# 21_Peripherals.net
KiCad netlist of a schematic drawn in Altium Designer
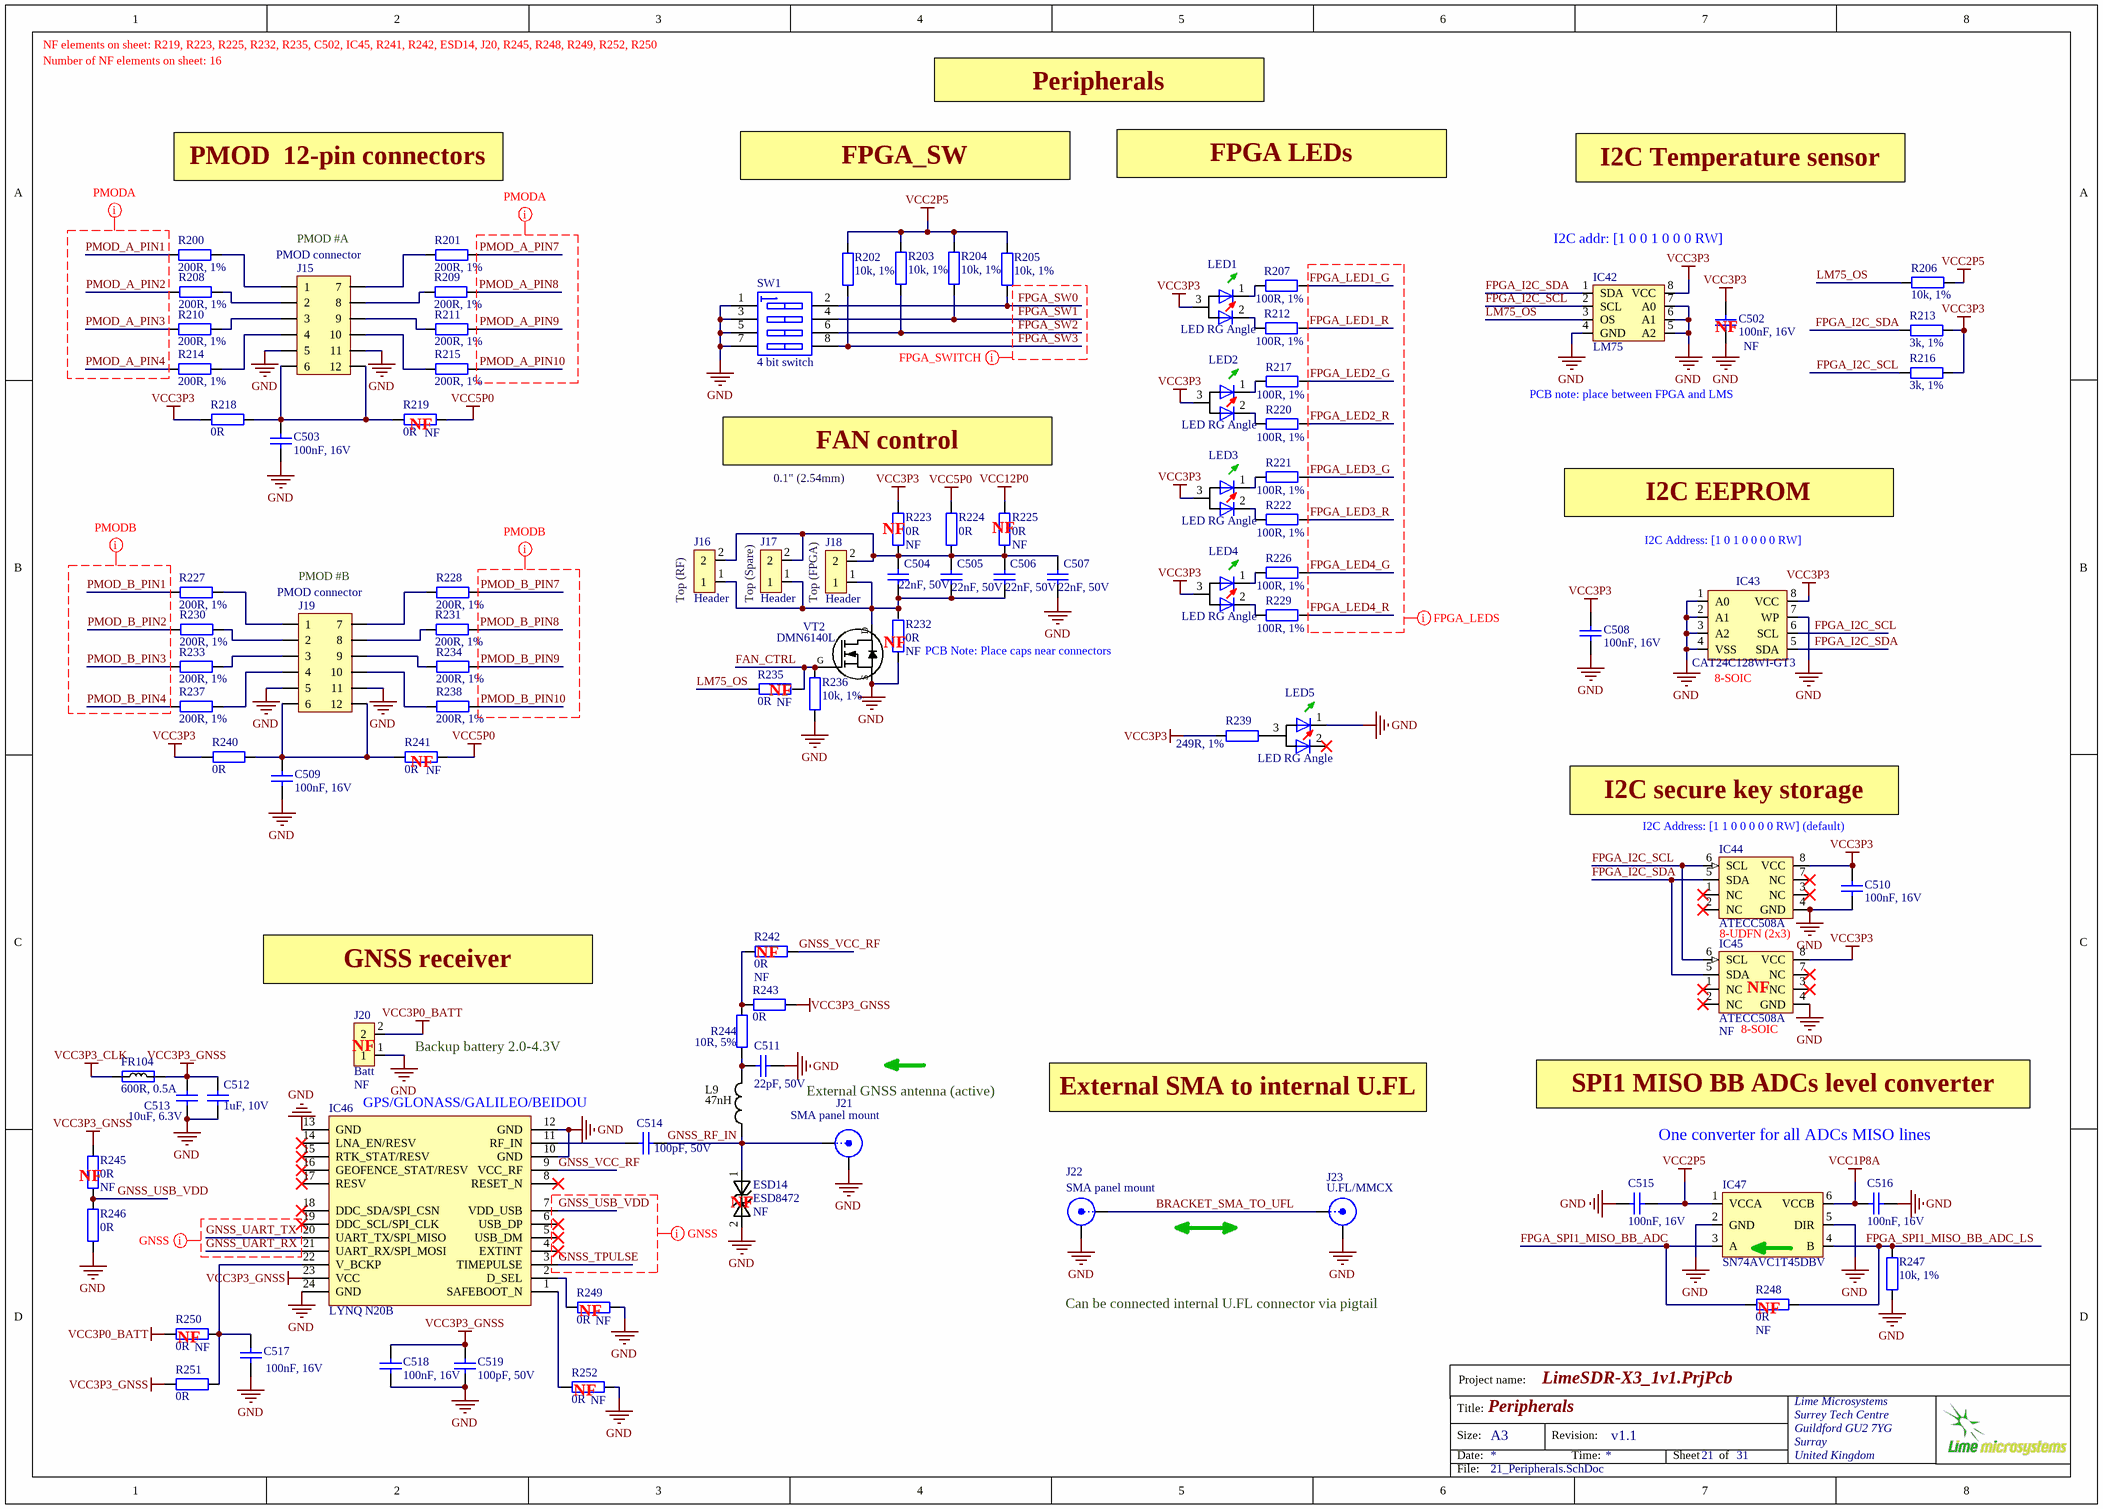
[diagram p0: 21_Peripherals.SchDoc]

(export (version "E")
  (design (tool "Eeschema 10.0.6"))
  (components
    (comp (ref "C502")
      (value "100nF, 16V")
      (footprint "CAP0402")
      (fields
        (field (name "TOLERANCE") "10 %")
        (field (name "MANUFACTURER") "Murata Electronics")
        (field (name "ASSEMBLY INFO") "NF")
      )
      (libsource (lib "") (part "Cap_0603_1"))
    )
    (comp (ref "C503")
      (value "100nF, 16V")
      (footprint "CAP0402")
      (fields
        (field (name "TOLERANCE") "10 %")
        (field (name "MANUFACTURER") "Murata Electronics")
        (field (name "MANUFACTURER PART NUMBER") "GRM155R71C104KA88D")
      )
      (libsource (lib "") (part "Cap_0603_3"))
    )
    (comp (ref "C504")
      (value "22nF, 50V")
      (footprint "CAP0402")
      (fields (field (name "TOLERANCE") "±10%") (field (name "MANUFACTURER") "Kemet"))
      (libsource (lib "") (part "Cap_0402_2"))
    )
    (comp (ref "C505")
      (value "22nF, 50V")
      (footprint "CAP0402")
      (fields (field (name "TOLERANCE") "±10%") (field (name "MANUFACTURER") "Kemet"))
      (libsource (lib "") (part "Cap_0402_1"))
    )
    (comp (ref "C506")
      (value "22nF, 50V")
      (footprint "CAP0402")
      (fields (field (name "TOLERANCE") "±10%") (field (name "MANUFACTURER") "Kemet"))
      (libsource (lib "") (part "Cap_0402_1"))
    )
    (comp (ref "C507")
      (value "22nF, 50V")
      (footprint "CAP0402")
      (fields (field (name "TOLERANCE") "±10%") (field (name "MANUFACTURER") "Kemet"))
      (libsource (lib "") (part "Cap_0402_1"))
    )
    (comp (ref "C508")
      (value "100nF, 16V")
      (footprint "CAP0402")
      (fields (field (name "TOLERANCE") "10 %") (field (name "MANUFACTURER") "Murata Electronics"))
      (libsource (lib "") (part "Cap_0603_2"))
    )
    (comp (ref "C509")
      (value "100nF, 16V")
      (footprint "CAP0402")
      (fields
        (field (name "TOLERANCE") "10 %")
        (field (name "MANUFACTURER") "Murata Electronics")
        (field (name "MANUFACTURER PART NUMBER") "GRM155R71C104KA88D")
      )
      (libsource (lib "") (part "Cap_0603_3"))
    )
    (comp (ref "C510")
      (value "100nF, 16V")
      (footprint "CAP0402")
      (fields (field (name "TOLERANCE") "10 %") (field (name "MANUFACTURER") "Murata Electronics"))
      (libsource (lib "") (part "Cap_0603_2"))
    )
    (comp (ref "C511")
      (value "22pF, 50V")
      (footprint "CAP0402")
      (fields (field (name "TOLERANCE") "±5%") (field (name "MANUFACTURER") "Yageo"))
      (libsource (lib "LimeMicroAltiumLib_schLib") (part "Cap_0402"))
    )
    (comp (ref "C512")
      (value "1uF, 10V")
      (footprint "CAP0402")
      (description "CAP CER 1UF 10V X5R 0402")
      (fields (field (name "MANUFACTURER") "TDK"))
      (libsource (lib "LimeMicroAltiumLib_schLib") (part "Cap_0402"))
    )
    (comp (ref "C513")
      (value "10uF, 6.3V")
      (footprint "CAP0603")
      (fields (field (name "TOLERANCE") "±20%") (field (name "MANUFACTURER") "Yageo"))
      (libsource (lib "") (part "Cap_0603_3"))
    )
    (comp (ref "C514")
      (value "100pF, 50V")
      (footprint "CAP0402")
      (fields (field (name "TOLERANCE") "±5%") (field (name "MANUFACTURER") "Yageo"))
      (libsource (lib "LimeMicroAltiumLib_schLib") (part "Cap_0402"))
    )
    (comp (ref "C515")
      (value "100nF, 16V")
      (footprint "CAP0402")
      (fields (field (name "TOLERANCE") "10 %") (field (name "MANUFACTURER") "Murata Electronics"))
      (libsource (lib "LimeFPGAboard_schLib") (part "Cap_0603"))
    )
    (comp (ref "C516")
      (value "100nF, 16V")
      (footprint "CAP0402")
      (fields (field (name "TOLERANCE") "10 %") (field (name "MANUFACTURER") "Murata Electronics"))
      (libsource (lib "LimeFPGAboard_schLib") (part "Cap_0603"))
    )
    (comp (ref "C517")
      (value "100nF, 16V")
      (footprint "CAP0402")
      (fields
        (field (name "TOLERANCE") "10 %")
        (field (name "MANUFACTURER") "Murata Electronics")
        (field (name "MANUFACTURER PART NUMBER") "GRM155R71C104KA88D")
      )
      (libsource (lib "") (part "Cap_0603_3"))
    )
    (comp (ref "C518")
      (value "100nF, 16V")
      (footprint "CAP0402")
      (fields
        (field (name "MANUFACTURER") "Murata Electronics")
        (field (name "TOLERANCE") "10 %")
        (field (name "MANUFACTURER PART NUMBER") "GRM155R71C104KA88D")
      )
      (libsource (lib "LimeMicroAltiumLib_schLib") (part "Cap_0402"))
    )
    (comp (ref "C519")
      (value "100pF, 50V")
      (footprint "CAP0402")
      (fields (field (name "TOLERANCE") "±5%") (field (name "MANUFACTURER") "Yageo"))
      (libsource (lib "LimeMicroAltiumLib_schLib") (part "Cap_0402"))
    )
    (comp (ref "ESD14")
      (value "ESD8472")
      (footprint "ESD8472_X3DFN2")
      (fields
        (field (name "MANUFACTURER") "ON Semiconductor")
        (field (name "MANUFACTURER PART NUMBER") "ESD8472MUT5G")
        (field (name "ASSEMBLY INFO") "NF")
      )
      (libsource (lib "LimeMicroAltiumLib_schLib") (part "ESD8472"))
    )
    (comp (ref "FR104")
      (value "600R, 0.5A")
      (footprint "RES0402")
      (fields
        (field (name "MANUFACTURER") "Murata")
        (field (name "TOLERANCE") "25%")
        (field (name "Comment") "Ferrite")
      )
      (libsource (lib "LimeMicroAltiumLib_schLib") (part "Ferrite"))
    )
    (comp (ref "IC42")
      (value "LM75")
      (footprint "HWSON8_LM75")
      (fields (field (name "MANUFACTURER") "NXP Semiconductors"))
      (libsource (lib "LimeMicroAltiumLib_schLib") (part "LM75"))
    )
    (comp (ref "IC43")
      (value "CAT24C128WI-GT3")
      (footprint "SOIC127P600-8DL_v2")
      (fields (field (name "MANUFACTURER") "ON Semiconductor") (field (name "BASE PART NUMBER") "CAT24C128"))
      (libsource (lib "LimeMicroAltiumLib_schLib") (part "24FC64F"))
    )
    (comp (ref "IC44")
      (value "ATECC508A")
      (footprint "ATECC508A_UDFN8")
      (fields (field (name "MANUFACTURER") "Microchip"))
      (libsource (lib "LimeMicroAltiumLib_schLib_r01") (part "ATECC508A_authentication_IC"))
    )
    (comp (ref "IC45")
      (value "ATECC508A")
      (footprint "SOIC127P600-8DL_v2")
      (fields
        (field (name "ASSEMBLY INFO") "NF")
        (field (name "MANUFACTURER") "Microchip Technology")
        (field (name "BASE PART NUMBER") "ATECC508")
      )
      (libsource (lib "") (part "ATECC508A_authentication_IC_1"))
    )
    (comp (ref "IC46")
      (value "LYNQ N20B")
      (footprint "NEO-7M/8M")
      (description "GNSS engine for GPS/QZSS, GLONASS")
      (fields (field (name "MANUFACTURER") "RF channe;"))
      (libsource (lib "LimeMicroAltiumLib_schLib") (part "NEO-M8P_M8M"))
    )
    (comp (ref "IC47")
      (value "SN74AVC1T45DBV")
      (footprint "SOT23-6")
      (fields (field (name "MANUFACTURER") "Texas Instruments"))
      (libsource (lib "LimeMicroAltiumLib_schLib_r01") (part "SN74AVC1T45DBV"))
    )
    (comp (ref "J15")
      (value "PMOD connector")
      (footprint "PMODconn_right_angle_TH")
      (description "Header, 4-Pin, Dual row")
      (fields (field (name "MANUFACTURER") "Sullins Connector Solutions"))
      (libsource (lib "LimeMicroAltiumLib_schLib") (part "PMOD_connector"))
    )
    (comp (ref "J16")
      (value "Header")
      (footprint "HDR_1x2")
      (fields (field (name "MANUFACTURER") "Wurth Electronics"))
      (libsource (lib "LimeFPGAboard_schLib") (part "Jumper"))
    )
    (comp (ref "J17")
      (value "Header")
      (footprint "HDR_1x2")
      (fields (field (name "MANUFACTURER") "Wurth Electronics"))
      (libsource (lib "LimeFPGAboard_schLib") (part "Jumper"))
    )
    (comp (ref "J18")
      (value "Header")
      (footprint "HDR_1x2")
      (fields (field (name "MANUFACTURER") "Wurth Electronics"))
      (libsource (lib "LimeFPGAboard_schLib") (part "Jumper"))
    )
    (comp (ref "J19")
      (value "PMOD connector")
      (footprint "PMODconn_right_angle_TH")
      (description "Header, 4-Pin, Dual row")
      (fields (field (name "MANUFACTURER") "Sullins Connector Solutions"))
      (libsource (lib "LimeMicroAltiumLib_schLib") (part "PMOD_connector"))
    )
    (comp (ref "J20")
      (value "Batt")
      (footprint "HDR_1x2")
      (fields (field (name "ASSEMBLY INFO") "NF") (field (name "MANUFACTURER") "3M"))
      (libsource (lib "") (part "Jumper_1"))
    )
    (comp (ref "J21")
      (value "SMA panel mount")
      (footprint "SMA_connector_side")
      (description "CONN SMA JACK STR 50OHM EDGE MNT")
      (fields (field (name "MANUFACTURER") "Linx"))
      (libsource (lib "LimeMicroAltiumLib_schLib") (part "RF_IF_connector"))
    )
    (comp (ref "J22")
      (value "SMA panel mount")
      (footprint "SMA_connector_side")
      (description "CONN SMA JACK STR 50OHM EDGE MNT")
      (fields (field (name "MANUFACTURER") "Linx"))
      (libsource (lib "LimeMicroAltiumLib_schLib") (part "RF_IF_connector"))
    )
    (comp (ref "J23")
      (value "U.FL/MMCX")
      (footprint "MMCX_UFL_conn_u")
      (description "CONN UMC RCPT STR 50 OHM SMD")
      (fields (field (name "MANUFACTURER") "Molex, LLC"))
      (libsource (lib "") (part "RF_IF_connector_1"))
    )
    (comp (ref "L9")
      (value "47nH")
      (footprint "RES0402")
      (fields
        (field (name "MANUFACTURER") "COILCRAFT")
        (field (name "MANUFACTURER PART NUMBER") "0402HP-47NXJLU")
      )
      (libsource (lib "LimeMicroAltiumLib_schLib") (part "Inductor_0603"))
    )
    (comp (ref "LED1")
      (value "LED RG Angle")
      (footprint "LED_RG_RIGHT_ANGLE_v3")
      (fields (field (name "MANUFACTURER") "Stanley Electric"))
      (libsource (lib "LimeMicroAltiumLib_schLib_r03") (part "LED_green_red_right_angle_v2"))
    )
    (comp (ref "LED2")
      (value "LED RG Angle")
      (footprint "LED_RG_RIGHT_ANGLE_v3")
      (fields (field (name "MANUFACTURER") "Stanley Electric"))
      (libsource (lib "LimeMicroAltiumLib_schLib_r03") (part "LED_green_red_right_angle_v2"))
    )
    (comp (ref "LED3")
      (value "LED RG Angle")
      (footprint "LED_RG_RIGHT_ANGLE_v3")
      (fields (field (name "MANUFACTURER") "Stanley Electric"))
      (libsource (lib "LimeMicroAltiumLib_schLib_r03") (part "LED_green_red_right_angle_v2"))
    )
    (comp (ref "LED4")
      (value "LED RG Angle")
      (footprint "LED_RG_RIGHT_ANGLE_v3")
      (fields (field (name "MANUFACTURER") "Stanley Electric"))
      (libsource (lib "LimeMicroAltiumLib_schLib_r03") (part "LED_green_red_right_angle_v2"))
    )
    (comp (ref "LED5")
      (value "LED RG Angle")
      (footprint "LED_RG_RIGHT_ANGLE_v3")
      (fields (field (name "MANUFACTURER") "Stanley Electric"))
      (libsource (lib "LimeMicroAltiumLib_schLib_r03") (part "LED_green_red_right_angle_v2"))
    )
    (comp (ref "R200")
      (value "200R, 1%")
      (footprint "RES0402")
      (fields (field (name "MANUFACTURER") "Yageo") (field (name "TOLERANCE") "1%"))
      (libsource (lib "LimeMicroAltiumLib_schLib") (part "Res_0402"))
    )
    (comp (ref "R201")
      (value "200R, 1%")
      (footprint "RES0402")
      (fields (field (name "MANUFACTURER") "Yageo") (field (name "TOLERANCE") "1%"))
      (libsource (lib "LimeMicroAltiumLib_schLib") (part "Res_0402"))
    )
    (comp (ref "R202")
      (value "10k, 1%")
      (footprint "RES0402")
      (fields (field (name "MANUFACTURER") "Yageo") (field (name "TOLERANCE") "±1%"))
      (libsource (lib "LimeMicroAltiumLib_schLib") (part "Res_0402"))
    )
    (comp (ref "R203")
      (value "10k, 1%")
      (footprint "RES0402")
      (fields (field (name "MANUFACTURER") "Yageo") (field (name "TOLERANCE") "±1%"))
      (libsource (lib "LimeMicroAltiumLib_schLib") (part "Res_0402"))
    )
    (comp (ref "R204")
      (value "10k, 1%")
      (footprint "RES0402")
      (fields (field (name "MANUFACTURER") "Yageo") (field (name "TOLERANCE") "±1%"))
      (libsource (lib "LimeMicroAltiumLib_schLib") (part "Res_0402"))
    )
    (comp (ref "R205")
      (value "10k, 1%")
      (footprint "RES0402")
      (fields (field (name "MANUFACTURER") "Yageo") (field (name "TOLERANCE") "±1%"))
      (libsource (lib "LimeMicroAltiumLib_schLib") (part "Res_0402"))
    )
    (comp (ref "R206")
      (value "10k, 1%")
      (footprint "RES0402")
      (fields (field (name "MANUFACTURER") "Yageo") (field (name "TOLERANCE") "±1%"))
      (libsource (lib "") (part "Res_0402_1"))
    )
    (comp (ref "R207")
      (value "100R, 1%")
      (footprint "RES0402")
      (fields (field (name "TOLERANCE") "±1%") (field (name "MANUFACTURER") "Stackpole Electronics Inc."))
      (libsource (lib "") (part "Res_0402_1"))
    )
    (comp (ref "R208")
      (value "200R, 1%")
      (footprint "RES0402")
      (fields (field (name "MANUFACTURER") "Yageo") (field (name "TOLERANCE") "1%"))
      (libsource (lib "LimeMicroAltiumLib_schLib") (part "Res_0402"))
    )
    (comp (ref "R209")
      (value "200R, 1%")
      (footprint "RES0402")
      (fields (field (name "MANUFACTURER") "Yageo") (field (name "TOLERANCE") "1%"))
      (libsource (lib "LimeMicroAltiumLib_schLib") (part "Res_0402"))
    )
    (comp (ref "R210")
      (value "200R, 1%")
      (footprint "RES0402")
      (fields (field (name "MANUFACTURER") "Yageo") (field (name "TOLERANCE") "1%"))
      (libsource (lib "LimeMicroAltiumLib_schLib") (part "Res_0402"))
    )
    (comp (ref "R211")
      (value "200R, 1%")
      (footprint "RES0402")
      (fields (field (name "MANUFACTURER") "Yageo") (field (name "TOLERANCE") "1%"))
      (libsource (lib "LimeMicroAltiumLib_schLib") (part "Res_0402"))
    )
    (comp (ref "R212")
      (value "100R, 1%")
      (footprint "RES0402")
      (fields (field (name "TOLERANCE") "±1%") (field (name "MANUFACTURER") "Stackpole Electronics Inc."))
      (libsource (lib "") (part "Res_0402_1"))
    )
    (comp (ref "R213")
      (value "3k, 1%")
      (footprint "RES0402")
      (fields (field (name "TOLERANCE") "±1%") (field (name "MANUFACTURER") "Vishay Dale"))
      (libsource (lib "") (part "Res_0402_1"))
    )
    (comp (ref "R214")
      (value "200R, 1%")
      (footprint "RES0402")
      (fields (field (name "MANUFACTURER") "Yageo") (field (name "TOLERANCE") "1%"))
      (libsource (lib "LimeMicroAltiumLib_schLib") (part "Res_0402"))
    )
    (comp (ref "R215")
      (value "200R, 1%")
      (footprint "RES0402")
      (fields (field (name "MANUFACTURER") "Yageo") (field (name "TOLERANCE") "1%"))
      (libsource (lib "LimeMicroAltiumLib_schLib") (part "Res_0402"))
    )
    (comp (ref "R216")
      (value "3k, 1%")
      (footprint "RES0402")
      (fields (field (name "TOLERANCE") "±1%") (field (name "MANUFACTURER") "Vishay Dale"))
      (libsource (lib "") (part "Res_0402_1"))
    )
    (comp (ref "R217")
      (value "100R, 1%")
      (footprint "RES0402")
      (fields (field (name "TOLERANCE") "±1%") (field (name "MANUFACTURER") "Stackpole Electronics Inc."))
      (libsource (lib "") (part "Res_0402_1"))
    )
    (comp (ref "R218")
      (value "0R")
      (footprint "RES0402")
      (fields (field (name "MANUFACTURER") "Yageo"))
      (libsource (lib "LimeFPGAboard_schLib") (part "Res_0402"))
    )
    (comp (ref "R219")
      (value "0R")
      (footprint "RES0402")
      (fields (field (name "MANUFACTURER") "Yageo") (field (name "ASSEMBLY INFO") "NF"))
      (libsource (lib "LimeFPGAboard_schLib") (part "Res_0402"))
    )
    (comp (ref "R220")
      (value "100R, 1%")
      (footprint "RES0402")
      (fields (field (name "TOLERANCE") "±1%") (field (name "MANUFACTURER") "Stackpole Electronics Inc."))
      (libsource (lib "") (part "Res_0402_1"))
    )
    (comp (ref "R221")
      (value "100R, 1%")
      (footprint "RES0402")
      (fields (field (name "TOLERANCE") "±1%") (field (name "MANUFACTURER") "Stackpole Electronics Inc."))
      (libsource (lib "") (part "Res_0402_1"))
    )
    (comp (ref "R222")
      (value "100R, 1%")
      (footprint "RES0402")
      (fields (field (name "TOLERANCE") "±1%") (field (name "MANUFACTURER") "Stackpole Electronics Inc."))
      (libsource (lib "") (part "Res_0402_1"))
    )
    (comp (ref "R223")
      (value "0R")
      (footprint "RES0402")
      (fields
        (field (name "ASSEMBLY INFO") "NF")
        (field (name "MANUFACTURER") "Yageo")
        (field (name "TOLERANCE") "Jumper")
      )
      (libsource (lib "") (part "Res_0402_1"))
    )
    (comp (ref "R224")
      (value "0R")
      (footprint "RES0402")
      (fields (field (name "MANUFACTURER") "Yageo") (field (name "TOLERANCE") "Jumper"))
      (libsource (lib "") (part "Res_0402_1"))
    )
    (comp (ref "R225")
      (value "0R")
      (footprint "RES0402")
      (fields
        (field (name "ASSEMBLY INFO") "NF")
        (field (name "MANUFACTURER") "Yageo")
        (field (name "TOLERANCE") "Jumper")
      )
      (libsource (lib "") (part "Res_0402_1"))
    )
    (comp (ref "R226")
      (value "100R, 1%")
      (footprint "RES0402")
      (fields (field (name "TOLERANCE") "±1%") (field (name "MANUFACTURER") "Stackpole Electronics Inc."))
      (libsource (lib "") (part "Res_0402_1"))
    )
    (comp (ref "R227")
      (value "200R, 1%")
      (footprint "RES0402")
      (fields (field (name "MANUFACTURER") "Yageo") (field (name "TOLERANCE") "1%"))
      (libsource (lib "LimeMicroAltiumLib_schLib") (part "Res_0402"))
    )
    (comp (ref "R228")
      (value "200R, 1%")
      (footprint "RES0402")
      (fields (field (name "MANUFACTURER") "Yageo") (field (name "TOLERANCE") "1%"))
      (libsource (lib "LimeMicroAltiumLib_schLib") (part "Res_0402"))
    )
    (comp (ref "R229")
      (value "100R, 1%")
      (footprint "RES0402")
      (fields (field (name "TOLERANCE") "±1%") (field (name "MANUFACTURER") "Stackpole Electronics Inc."))
      (libsource (lib "") (part "Res_0402_1"))
    )
    (comp (ref "R230")
      (value "200R, 1%")
      (footprint "RES0402")
      (fields (field (name "MANUFACTURER") "Yageo") (field (name "TOLERANCE") "1%"))
      (libsource (lib "LimeMicroAltiumLib_schLib") (part "Res_0402"))
    )
    (comp (ref "R231")
      (value "200R, 1%")
      (footprint "RES0402")
      (fields (field (name "MANUFACTURER") "Yageo") (field (name "TOLERANCE") "1%"))
      (libsource (lib "LimeMicroAltiumLib_schLib") (part "Res_0402"))
    )
    (comp (ref "R232")
      (value "0R")
      (footprint "RES0402")
      (fields
        (field (name "ASSEMBLY INFO") "NF")
        (field (name "MANUFACTURER") "Yageo")
        (field (name "TOLERANCE") "Jumper")
      )
      (libsource (lib "") (part "Res_0402_1"))
    )
    (comp (ref "R233")
      (value "200R, 1%")
      (footprint "RES0402")
      (fields (field (name "MANUFACTURER") "Yageo") (field (name "TOLERANCE") "1%"))
      (libsource (lib "LimeMicroAltiumLib_schLib") (part "Res_0402"))
    )
    (comp (ref "R234")
      (value "200R, 1%")
      (footprint "RES0402")
      (fields (field (name "MANUFACTURER") "Yageo") (field (name "TOLERANCE") "1%"))
      (libsource (lib "LimeMicroAltiumLib_schLib") (part "Res_0402"))
    )
    (comp (ref "R235")
      (value "0R")
      (footprint "RES0402")
      (fields (field (name "MANUFACTURER") "Yageo") (field (name "ASSEMBLY INFO") "NF"))
      (libsource (lib "") (part "Res_0402_1"))
    )
    (comp (ref "R236")
      (value "10k, 1%")
      (footprint "RES0402")
      (fields (field (name "MANUFACTURER") "Yageo") (field (name "TOLERANCE") "±1%"))
      (libsource (lib "") (part "Res_0402_1"))
    )
    (comp (ref "R237")
      (value "200R, 1%")
      (footprint "RES0402")
      (fields (field (name "MANUFACTURER") "Yageo") (field (name "TOLERANCE") "1%"))
      (libsource (lib "LimeMicroAltiumLib_schLib") (part "Res_0402"))
    )
    (comp (ref "R238")
      (value "200R, 1%")
      (footprint "RES0402")
      (fields (field (name "MANUFACTURER") "Yageo") (field (name "TOLERANCE") "1%"))
      (libsource (lib "LimeMicroAltiumLib_schLib") (part "Res_0402"))
    )
    (comp (ref "R239")
      (value "249R, 1%")
      (footprint "RES0402")
      (fields (field (name "MANUFACTURER") "Stackpole Electronics Inc") (field (name "TOLERANCE") "±1%"))
      (libsource (lib "") (part "Res_0402_1"))
    )
    (comp (ref "R240")
      (value "0R")
      (footprint "RES0402")
      (fields (field (name "MANUFACTURER") "Yageo"))
      (libsource (lib "LimeFPGAboard_schLib") (part "Res_0402"))
    )
    (comp (ref "R241")
      (value "0R")
      (footprint "RES0402")
      (fields (field (name "MANUFACTURER") "Yageo") (field (name "ASSEMBLY INFO") "NF"))
      (libsource (lib "LimeFPGAboard_schLib") (part "Res_0402"))
    )
    (comp (ref "R242")
      (value "0R")
      (footprint "RES0402")
      (fields
        (field (name "ASSEMBLY INFO") "NF")
        (field (name "MANUFACTURER") "Yageo")
        (field (name "TOLERANCE") "Jumper")
      )
      (libsource (lib "LimeMicroAltiumLib_schLib") (part "Res_0402"))
    )
    (comp (ref "R243")
      (value "0R")
      (footprint "RES0402")
      (fields (field (name "MANUFACTURER") "Yageo") (field (name "TOLERANCE") "Jumper"))
      (libsource (lib "LimeMicroAltiumLib_schLib") (part "Res_0402"))
    )
    (comp (ref "R244")
      (value "10R, 5%")
      (footprint "RES0402")
      (fields (field (name "TOLERANCE") "±5%") (field (name "MANUFACTURER") "Yageo"))
      (libsource (lib "LimeMicroAltiumLib_schLib") (part "Res_0402"))
    )
    (comp (ref "R245")
      (value "0R")
      (footprint "RES0402")
      (fields
        (field (name "ASSEMBLY INFO") "NF")
        (field (name "MANUFACTURER") "Yageo")
        (field (name "TOLERANCE") "Jumper")
      )
      (libsource (lib "LimeMicroAltiumLib_schLib") (part "Res_0402"))
    )
    (comp (ref "R246")
      (value "0R")
      (footprint "RES0402")
      (fields (field (name "MANUFACTURER") "Yageo") (field (name "TOLERANCE") "Jumper"))
      (libsource (lib "LimeMicroAltiumLib_schLib") (part "Res_0402"))
    )
    (comp (ref "R247")
      (value "10k, 1%")
      (footprint "RES0402")
      (fields (field (name "MANUFACTURER") "Yageo") (field (name "TOLERANCE") "±1%"))
      (libsource (lib "") (part "Res_0402_1"))
    )
    (comp (ref "R248")
      (value "0R")
      (footprint "RES0402")
      (fields
        (field (name "ASSEMBLY INFO") "NF")
        (field (name "MANUFACTURER") "Yageo")
        (field (name "TOLERANCE") "Jumper")
      )
      (libsource (lib "") (part "Res_0402_1"))
    )
    (comp (ref "R249")
      (value "0R")
      (footprint "RES0402")
      (fields
        (field (name "ASSEMBLY INFO") "NF")
        (field (name "MANUFACTURER") "Yageo")
        (field (name "TOLERANCE") "Jumper")
      )
      (libsource (lib "LimeMicroAltiumLib_schLib") (part "Res_0402"))
    )
    (comp (ref "R250")
      (value "0R")
      (footprint "RES0402")
      (fields
        (field (name "ASSEMBLY INFO") "NF")
        (field (name "MANUFACTURER") "Yageo")
        (field (name "TOLERANCE") "Jumper")
      )
      (libsource (lib "LimeMicroAltiumLib_schLib") (part "Res_0402"))
    )
    (comp (ref "R251")
      (value "0R")
      (footprint "RES0402")
      (fields (field (name "MANUFACTURER") "Yageo") (field (name "TOLERANCE") "Jumper"))
      (libsource (lib "LimeMicroAltiumLib_schLib") (part "Res_0402"))
    )
    (comp (ref "R252")
      (value "0R")
      (footprint "RES0402")
      (fields
        (field (name "ASSEMBLY INFO") "NF")
        (field (name "MANUFACTURER") "Yageo")
        (field (name "TOLERANCE") "Jumper")
      )
      (libsource (lib "LimeMicroAltiumLib_schLib") (part "Res_0402"))
    )
    (comp (ref "SW1")
      (value "4 bit switch")
      (footprint "DS02C-254-1L-04BE_DIP_SWITCH_4PIN")
      (fields (field (name "MANUFACTURER") "CUI Devices"))
      (libsource (lib "LimeMicroAltiumLib_schLib_r03") (part "SW_SM_4bit_v2"))
    )
    (comp (ref "VT2")
      (value "DMN6140L")
      (footprint "SOT23-3")
      (description "NDS331N")
      (fields
        (field (name "MANUFACTURER PART NUMBER") "DMN6140L-13")
        (field (name "MANUFACTURER") "Diodes Incorporated")
      )
      (libsource (lib "LimeFPGAboard_schLib") (part "NDS331N"))
    )
  )
  (nets
    (net (code "1") (name "/BRACKET_SMA_TO_UFL") (class "Default")
      (node (ref "J22") (pin "1") (pinfunction "X_1") (pintype "passive"))
      (node (ref "J23") (pin "1") (pinfunction "X_1") (pintype "passive"))
    )
    (net (code "2") (name "/FAN_CTRL") (class "Default")
      (node (ref "R235") (pin "2") (pinfunction "2_2") (pintype "passive"))
      (node (ref "R236") (pin "1") (pinfunction "1_1") (pintype "passive"))
      (node (ref "VT2") (pin "G") (pinfunction "G_G") (pintype "passive"))
    )
    (net (code "3") (name "/FPGA_I2C_SCL") (class "Default")
      (node (ref "IC42") (pin "2") (pinfunction "SCL_2") (pintype "passive"))
      (node (ref "IC43") (pin "6") (pinfunction "SCL_6") (pintype "passive"))
      (node (ref "IC44") (pin "6") (pinfunction "SCL_6") (pintype "input"))
      (node (ref "IC45") (pin "6") (pinfunction "SCL_6") (pintype "input"))
      (node (ref "R216") (pin "2") (pinfunction "2_2") (pintype "passive"))
    )
    (net (code "4") (name "/FPGA_I2C_SDA") (class "Default")
      (node (ref "IC42") (pin "1") (pinfunction "SDA_1") (pintype "passive"))
      (node (ref "IC43") (pin "5") (pinfunction "SDA_5") (pintype "passive"))
      (node (ref "IC44") (pin "5") (pinfunction "SDA_5") (pintype "bidirectional"))
      (node (ref "IC45") (pin "5") (pinfunction "SDA_5") (pintype "bidirectional"))
      (node (ref "R213") (pin "2") (pinfunction "2_2") (pintype "passive"))
    )
    (net (code "5") (name "/FPGA_LED1_G") (class "Default")
      (node (ref "R207") (pin "2") (pinfunction "2_2") (pintype "passive"))
    )
    (net (code "6") (name "/FPGA_LED1_R") (class "Default")
      (node (ref "R212") (pin "2") (pinfunction "2_2") (pintype "passive"))
    )
    (net (code "7") (name "/FPGA_LED2_G") (class "Default")
      (node (ref "R217") (pin "2") (pinfunction "2_2") (pintype "passive"))
    )
    (net (code "8") (name "/FPGA_LED2_R") (class "Default")
      (node (ref "R220") (pin "2") (pinfunction "2_2") (pintype "passive"))
    )
    (net (code "9") (name "/FPGA_LED3_G") (class "Default")
      (node (ref "R221") (pin "2") (pinfunction "2_2") (pintype "passive"))
    )
    (net (code "10") (name "/FPGA_LED3_R") (class "Default")
      (node (ref "R222") (pin "2") (pinfunction "2_2") (pintype "passive"))
    )
    (net (code "11") (name "/FPGA_LED4_G") (class "Default")
      (node (ref "R226") (pin "2") (pinfunction "2_2") (pintype "passive"))
    )
    (net (code "12") (name "/FPGA_LED4_R") (class "Default")
      (node (ref "R229") (pin "2") (pinfunction "2_2") (pintype "passive"))
    )
    (net (code "13") (name "/FPGA_SPI1_MISO_BB_ADC") (class "Default")
      (node (ref "IC47") (pin "3") (pinfunction "A_3") (pintype "bidirectional"))
      (node (ref "R248") (pin "2") (pinfunction "2_2") (pintype "passive"))
    )
    (net (code "14") (name "/FPGA_SPI1_MISO_BB_ADC_LS") (class "Default")
      (node (ref "IC47") (pin "4") (pinfunction "B_4") (pintype "bidirectional"))
      (node (ref "R247") (pin "2") (pinfunction "2_2") (pintype "passive"))
      (node (ref "R248") (pin "1") (pinfunction "1_1") (pintype "passive"))
    )
    (net (code "15") (name "/FPGA_SW0") (class "Default")
      (node (ref "R205") (pin "2") (pinfunction "2_2") (pintype "passive"))
      (node (ref "SW1") (pin "2") (pinfunction "B1_2") (pintype "passive"))
    )
    (net (code "16") (name "/FPGA_SW1") (class "Default")
      (node (ref "R204") (pin "2") (pinfunction "2_2") (pintype "passive"))
      (node (ref "SW1") (pin "4") (pinfunction "B2_4") (pintype "passive"))
    )
    (net (code "17") (name "/FPGA_SW2") (class "Default")
      (node (ref "R203") (pin "2") (pinfunction "2_2") (pintype "passive"))
      (node (ref "SW1") (pin "6") (pinfunction "B3_6") (pintype "passive"))
    )
    (net (code "18") (name "/FPGA_SW3") (class "Default")
      (node (ref "R202") (pin "2") (pinfunction "2_2") (pintype "passive"))
      (node (ref "SW1") (pin "8") (pinfunction "B4_8") (pintype "passive"))
    )
    (net (code "19") (name "/GNSS_RF_IN") (class "Default")
      (node (ref "C514") (pin "1") (pinfunction "1_1") (pintype "passive"))
      (node (ref "ESD14") (pin "1") (pinfunction "1_1") (pintype "passive"))
      (node (ref "J21") (pin "1") (pinfunction "X_1") (pintype "passive"))
      (node (ref "L9") (pin "1") (pinfunction "1_1") (pintype "passive"))
    )
    (net (code "20") (name "/GNSS_TPULSE") (class "Default")
      (node (ref "IC46") (pin "3") (pinfunction "TIMEPULSE_3") (pintype "passive"))
    )
    (net (code "21") (name "/GNSS_UART_RX") (class "Default")
      (node (ref "IC46") (pin "21") (pinfunction "UART_RX/SPI_MOSI_21") (pintype "passive"))
    )
    (net (code "22") (name "/GNSS_UART_TX") (class "Default")
      (node (ref "IC46") (pin "20") (pinfunction "UART_TX/SPI_MISO_20") (pintype "passive"))
    )
    (net (code "23") (name "/GNSS_USB_VDD") (class "Default")
      (node (ref "IC46") (pin "7") (pinfunction "VDD_USB_7") (pintype "passive"))
      (node (ref "R245") (pin "1") (pinfunction "1_1") (pintype "passive"))
      (node (ref "R246") (pin "1") (pinfunction "1_1") (pintype "passive"))
    )
    (net (code "24") (name "/GNSS_VCC_RF") (class "Default")
      (node (ref "IC46") (pin "9") (pinfunction "VCC_RF_9") (pintype "passive"))
      (node (ref "R242") (pin "2") (pinfunction "2_2") (pintype "passive"))
    )
    (net (code "25") (name "/LM75_OS") (class "Default")
      (node (ref "IC42") (pin "3") (pinfunction "OS_3") (pintype "passive"))
      (node (ref "R206") (pin "1") (pinfunction "1_1") (pintype "passive"))
      (node (ref "R235") (pin "1") (pinfunction "1_1") (pintype "passive"))
    )
    (net (code "26") (name "/PMOD_A_PIN1") (class "Default")
      (node (ref "R200") (pin "1") (pinfunction "1_1") (pintype "passive"))
    )
    (net (code "27") (name "/PMOD_A_PIN2") (class "Default")
      (node (ref "R208") (pin "1") (pinfunction "1_1") (pintype "passive"))
    )
    (net (code "28") (name "/PMOD_A_PIN3") (class "Default")
      (node (ref "R210") (pin "1") (pinfunction "1_1") (pintype "passive"))
    )
    (net (code "29") (name "/PMOD_A_PIN4") (class "Default")
      (node (ref "R214") (pin "1") (pinfunction "1_1") (pintype "passive"))
    )
    (net (code "30") (name "/PMOD_A_PIN7") (class "Default")
      (node (ref "R201") (pin "2") (pinfunction "2_2") (pintype "passive"))
    )
    (net (code "31") (name "/PMOD_A_PIN8") (class "Default")
      (node (ref "R209") (pin "2") (pinfunction "2_2") (pintype "passive"))
    )
    (net (code "32") (name "/PMOD_A_PIN9") (class "Default")
      (node (ref "R211") (pin "2") (pinfunction "2_2") (pintype "passive"))
    )
    (net (code "33") (name "/PMOD_A_PIN10") (class "Default")
      (node (ref "R215") (pin "2") (pinfunction "2_2") (pintype "passive"))
    )
    (net (code "34") (name "/PMOD_B_PIN1") (class "Default")
      (node (ref "R227") (pin "1") (pinfunction "1_1") (pintype "passive"))
    )
    (net (code "35") (name "/PMOD_B_PIN2") (class "Default")
      (node (ref "R230") (pin "1") (pinfunction "1_1") (pintype "passive"))
    )
    (net (code "36") (name "/PMOD_B_PIN3") (class "Default")
      (node (ref "R233") (pin "1") (pinfunction "1_1") (pintype "passive"))
    )
    (net (code "37") (name "/PMOD_B_PIN4") (class "Default")
      (node (ref "R237") (pin "1") (pinfunction "1_1") (pintype "passive"))
    )
    (net (code "38") (name "/PMOD_B_PIN7") (class "Default")
      (node (ref "R228") (pin "2") (pinfunction "2_2") (pintype "passive"))
    )
    (net (code "39") (name "/PMOD_B_PIN8") (class "Default")
      (node (ref "R231") (pin "2") (pinfunction "2_2") (pintype "passive"))
    )
    (net (code "40") (name "/PMOD_B_PIN9") (class "Default")
      (node (ref "R234") (pin "2") (pinfunction "2_2") (pintype "passive"))
    )
    (net (code "41") (name "/PMOD_B_PIN10") (class "Default")
      (node (ref "R238") (pin "2") (pinfunction "2_2") (pintype "passive"))
    )
    (net (code "42") (name "GND") (class "Default")
      (node (ref "C502") (pin "2") (pinfunction "2_2") (pintype "passive"))
      (node (ref "C503") (pin "2") (pinfunction "2_2") (pintype "passive"))
      (node (ref "C507") (pin "2") (pinfunction "2_2") (pintype "passive"))
      (node (ref "C508") (pin "2") (pinfunction "2_2") (pintype "passive"))
      (node (ref "C509") (pin "2") (pinfunction "2_2") (pintype "passive"))
      (node (ref "C510") (pin "2") (pinfunction "2_2") (pintype "passive"))
      (node (ref "C511") (pin "1") (pinfunction "1_1") (pintype "passive"))
      (node (ref "C512") (pin "1") (pinfunction "1_1") (pintype "passive"))
      (node (ref "C513") (pin "1") (pinfunction "1_1") (pintype "passive"))
      (node (ref "C515") (pin "1") (pinfunction "1_1") (pintype "passive"))
      (node (ref "C516") (pin "2") (pinfunction "2_2") (pintype "passive"))
      (node (ref "C517") (pin "2") (pinfunction "2_2") (pintype "passive"))
      (node (ref "C518") (pin "1") (pinfunction "1_1") (pintype "passive"))
      (node (ref "C519") (pin "2") (pinfunction "2_2") (pintype "passive"))
      (node (ref "ESD14") (pin "2") (pinfunction "2_2") (pintype "passive"))
      (node (ref "IC42") (pin "4") (pinfunction "GND_4") (pintype "passive"))
      (node (ref "IC42") (pin "5") (pinfunction "A2_5") (pintype "passive"))
      (node (ref "IC42") (pin "6") (pinfunction "A1_6") (pintype "passive"))
      (node (ref "IC42") (pin "7") (pinfunction "A0_7") (pintype "passive"))
      (node (ref "IC43") (pin "1") (pinfunction "A0_1") (pintype "passive"))
      (node (ref "IC43") (pin "2") (pinfunction "A1_2") (pintype "passive"))
      (node (ref "IC43") (pin "3") (pinfunction "A2_3") (pintype "passive"))
      (node (ref "IC43") (pin "4") (pinfunction "VSS_4") (pintype "passive"))
      (node (ref "IC43") (pin "7") (pinfunction "WP_7") (pintype "passive"))
      (node (ref "IC44") (pin "4") (pinfunction "GND_4") (pintype "passive"))
      (node (ref "IC45") (pin "4") (pinfunction "GND_4") (pintype "passive"))
      (node (ref "IC46") (pin "10") (pinfunction "GND_10") (pintype "passive"))
      (node (ref "IC46") (pin "12") (pinfunction "GND_12") (pintype "passive"))
      (node (ref "IC46") (pin "13") (pinfunction "GND_13") (pintype "passive"))
      (node (ref "IC46") (pin "24") (pinfunction "GND_24") (pintype "passive"))
      (node (ref "IC47") (pin "2") (pinfunction "GND_2") (pintype "passive"))
      (node (ref "IC47") (pin "5") (pinfunction "DIR_5") (pintype "input"))
      (node (ref "J15") (pin "11") (pinfunction "11_11") (pintype "passive"))
      (node (ref "J15") (pin "5") (pinfunction "5_5") (pintype "passive"))
      (node (ref "J19") (pin "11") (pinfunction "11_11") (pintype "passive"))
      (node (ref "J19") (pin "5") (pinfunction "5_5") (pintype "passive"))
      (node (ref "J20") (pin "1") (pinfunction "1_1") (pintype "passive"))
      (node (ref "J21") (pin "2") (pinfunction "Y_2") (pintype "passive"))
      (node (ref "J22") (pin "2") (pinfunction "Y_2") (pintype "passive"))
      (node (ref "J23") (pin "2") (pinfunction "Y_2") (pintype "passive"))
      (node (ref "LED5") (pin "1") (pinfunction "C1_1") (pintype "power_in"))
      (node (ref "R232") (pin "1") (pinfunction "1_1") (pintype "passive"))
      (node (ref "R236") (pin "2") (pinfunction "2_2") (pintype "passive"))
      (node (ref "R246") (pin "2") (pinfunction "2_2") (pintype "passive"))
      (node (ref "R247") (pin "1") (pinfunction "1_1") (pintype "passive"))
      (node (ref "R249") (pin "1") (pinfunction "1_1") (pintype "passive"))
      (node (ref "R252") (pin "1") (pinfunction "1_1") (pintype "passive"))
      (node (ref "SW1") (pin "1") (pinfunction "A1_1") (pintype "passive"))
      (node (ref "SW1") (pin "3") (pinfunction "A2_3") (pintype "passive"))
      (node (ref "SW1") (pin "5") (pinfunction "A3_5") (pintype "passive"))
      (node (ref "SW1") (pin "7") (pinfunction "A4_7") (pintype "passive"))
      (node (ref "VT2") (pin "S") (pinfunction "S_S") (pintype "passive"))
    )
    (net (code "43") (name "Net-(C503-Pad1)") (class "Default")
      (node (ref "C503") (pin "1") (pinfunction "1_1") (pintype "passive"))
      (node (ref "J15") (pin "12") (pinfunction "12_12") (pintype "passive"))
      (node (ref "J15") (pin "6") (pinfunction "6_6") (pintype "passive"))
      (node (ref "R218") (pin "1") (pinfunction "1_1") (pintype "passive"))
      (node (ref "R219") (pin "2") (pinfunction "2_2") (pintype "passive"))
    )
    (net (code "44") (name "Net-(C504-Pad1)") (class "Default")
      (node (ref "C504") (pin "1") (pinfunction "1_1") (pintype "passive"))
      (node (ref "C505") (pin "1") (pinfunction "1_1") (pintype "passive"))
      (node (ref "C506") (pin "1") (pinfunction "1_1") (pintype "passive"))
      (node (ref "C507") (pin "1") (pinfunction "1_1") (pintype "passive"))
      (node (ref "J16") (pin "2") (pinfunction "2_2") (pintype "passive"))
      (node (ref "J17") (pin "2") (pinfunction "2_2") (pintype "passive"))
      (node (ref "J18") (pin "2") (pinfunction "2_2") (pintype "passive"))
      (node (ref "R223") (pin "1") (pinfunction "1_1") (pintype "passive"))
      (node (ref "R224") (pin "1") (pinfunction "1_1") (pintype "passive"))
      (node (ref "R225") (pin "1") (pinfunction "1_1") (pintype "passive"))
    )
    (net (code "45") (name "Net-(C504-Pad2)") (class "Default")
      (node (ref "C504") (pin "2") (pinfunction "2_2") (pintype "passive"))
      (node (ref "C505") (pin "2") (pinfunction "2_2") (pintype "passive"))
      (node (ref "C506") (pin "2") (pinfunction "2_2") (pintype "passive"))
      (node (ref "J16") (pin "1") (pinfunction "1_1") (pintype "passive"))
      (node (ref "J17") (pin "1") (pinfunction "1_1") (pintype "passive"))
      (node (ref "J18") (pin "1") (pinfunction "1_1") (pintype "passive"))
      (node (ref "R232") (pin "2") (pinfunction "2_2") (pintype "passive"))
      (node (ref "VT2") (pin "D") (pinfunction "D_D") (pintype "passive"))
    )
    (net (code "46") (name "Net-(C509-Pad1)") (class "Default")
      (node (ref "C509") (pin "1") (pinfunction "1_1") (pintype "passive"))
      (node (ref "J19") (pin "12") (pinfunction "12_12") (pintype "passive"))
      (node (ref "J19") (pin "6") (pinfunction "6_6") (pintype "passive"))
      (node (ref "R240") (pin "1") (pinfunction "1_1") (pintype "passive"))
      (node (ref "R241") (pin "2") (pinfunction "2_2") (pintype "passive"))
    )
    (net (code "47") (name "Net-(C511-Pad2)") (class "Default")
      (node (ref "C511") (pin "2") (pinfunction "2_2") (pintype "passive"))
      (node (ref "L9") (pin "2") (pinfunction "2_2") (pintype "passive"))
      (node (ref "R244") (pin "2") (pinfunction "2_2") (pintype "passive"))
    )
    (net (code "48") (name "Net-(IC46-D_SEL)") (class "Default")
      (node (ref "IC46") (pin "2") (pinfunction "D_SEL_2") (pintype "passive"))
      (node (ref "R249") (pin "2") (pinfunction "2_2") (pintype "passive"))
    )
    (net (code "49") (name "Net-(IC46-RF_IN)") (class "Default")
      (node (ref "C514") (pin "2") (pinfunction "2_2") (pintype "passive"))
      (node (ref "IC46") (pin "11") (pinfunction "RF_IN_11") (pintype "passive"))
    )
    (net (code "50") (name "Net-(IC46-SAFEBOOT_N)") (class "Default")
      (node (ref "IC46") (pin "1") (pinfunction "SAFEBOOT_N_1") (pintype "passive"))
      (node (ref "R252") (pin "2") (pinfunction "2_2") (pintype "passive"))
    )
    (net (code "51") (name "Net-(IC46-V_BCKP)") (class "Default")
      (node (ref "C517") (pin "1") (pinfunction "1_1") (pintype "passive"))
      (node (ref "IC46") (pin "22") (pinfunction "V_BCKP_22") (pintype "passive"))
      (node (ref "R250") (pin "1") (pinfunction "1_1") (pintype "passive"))
      (node (ref "R251") (pin "1") (pinfunction "1_1") (pintype "passive"))
    )
    (net (code "52") (name "Net-(J15-Pad1)") (class "Default")
      (node (ref "J15") (pin "1") (pinfunction "1_1") (pintype "passive"))
      (node (ref "R200") (pin "2") (pinfunction "2_2") (pintype "passive"))
    )
    (net (code "53") (name "Net-(J15-Pad2)") (class "Default")
      (node (ref "J15") (pin "2") (pinfunction "2_2") (pintype "passive"))
      (node (ref "R208") (pin "2") (pinfunction "2_2") (pintype "passive"))
    )
    (net (code "54") (name "Net-(J15-Pad3)") (class "Default")
      (node (ref "J15") (pin "3") (pinfunction "3_3") (pintype "passive"))
      (node (ref "R210") (pin "2") (pinfunction "2_2") (pintype "passive"))
    )
    (net (code "55") (name "Net-(J15-Pad4)") (class "Default")
      (node (ref "J15") (pin "4") (pinfunction "4_4") (pintype "passive"))
      (node (ref "R214") (pin "2") (pinfunction "2_2") (pintype "passive"))
    )
    (net (code "56") (name "Net-(J15-Pad7)") (class "Default")
      (node (ref "J15") (pin "7") (pinfunction "7_7") (pintype "passive"))
      (node (ref "R201") (pin "1") (pinfunction "1_1") (pintype "passive"))
    )
    (net (code "57") (name "Net-(J15-Pad8)") (class "Default")
      (node (ref "J15") (pin "8") (pinfunction "8_8") (pintype "passive"))
      (node (ref "R209") (pin "1") (pinfunction "1_1") (pintype "passive"))
    )
    (net (code "58") (name "Net-(J15-Pad9)") (class "Default")
      (node (ref "J15") (pin "9") (pinfunction "9_9") (pintype "passive"))
      (node (ref "R211") (pin "1") (pinfunction "1_1") (pintype "passive"))
    )
    (net (code "59") (name "Net-(J15-Pad10)") (class "Default")
      (node (ref "J15") (pin "10") (pinfunction "10_10") (pintype "passive"))
      (node (ref "R215") (pin "1") (pinfunction "1_1") (pintype "passive"))
    )
    (net (code "60") (name "Net-(J19-Pad1)") (class "Default")
      (node (ref "J19") (pin "1") (pinfunction "1_1") (pintype "passive"))
      (node (ref "R227") (pin "2") (pinfunction "2_2") (pintype "passive"))
    )
    (net (code "61") (name "Net-(J19-Pad2)") (class "Default")
      (node (ref "J19") (pin "2") (pinfunction "2_2") (pintype "passive"))
      (node (ref "R230") (pin "2") (pinfunction "2_2") (pintype "passive"))
    )
    (net (code "62") (name "Net-(J19-Pad3)") (class "Default")
      (node (ref "J19") (pin "3") (pinfunction "3_3") (pintype "passive"))
      (node (ref "R233") (pin "2") (pinfunction "2_2") (pintype "passive"))
    )
    (net (code "63") (name "Net-(J19-Pad4)") (class "Default")
      (node (ref "J19") (pin "4") (pinfunction "4_4") (pintype "passive"))
      (node (ref "R237") (pin "2") (pinfunction "2_2") (pintype "passive"))
    )
    (net (code "64") (name "Net-(J19-Pad7)") (class "Default")
      (node (ref "J19") (pin "7") (pinfunction "7_7") (pintype "passive"))
      (node (ref "R228") (pin "1") (pinfunction "1_1") (pintype "passive"))
    )
    (net (code "65") (name "Net-(J19-Pad8)") (class "Default")
      (node (ref "J19") (pin "8") (pinfunction "8_8") (pintype "passive"))
      (node (ref "R231") (pin "1") (pinfunction "1_1") (pintype "passive"))
    )
    (net (code "66") (name "Net-(J19-Pad9)") (class "Default")
      (node (ref "J19") (pin "9") (pinfunction "9_9") (pintype "passive"))
      (node (ref "R234") (pin "1") (pinfunction "1_1") (pintype "passive"))
    )
    (net (code "67") (name "Net-(J19-Pad10)") (class "Default")
      (node (ref "J19") (pin "10") (pinfunction "10_10") (pintype "passive"))
      (node (ref "R238") (pin "1") (pinfunction "1_1") (pintype "passive"))
    )
    (net (code "68") (name "Net-(LED1-C1)") (class "Default")
      (node (ref "LED1") (pin "1") (pinfunction "C1_1") (pintype "power_in"))
      (node (ref "R207") (pin "1") (pinfunction "1_1") (pintype "passive"))
    )
    (net (code "69") (name "Net-(LED1-C2)") (class "Default")
      (node (ref "LED1") (pin "2") (pinfunction "C2_2") (pintype "power_in"))
      (node (ref "R212") (pin "1") (pinfunction "1_1") (pintype "passive"))
    )
    (net (code "70") (name "Net-(LED2-C1)") (class "Default")
      (node (ref "LED2") (pin "1") (pinfunction "C1_1") (pintype "power_in"))
      (node (ref "R217") (pin "1") (pinfunction "1_1") (pintype "passive"))
    )
    (net (code "71") (name "Net-(LED2-C2)") (class "Default")
      (node (ref "LED2") (pin "2") (pinfunction "C2_2") (pintype "power_in"))
      (node (ref "R220") (pin "1") (pinfunction "1_1") (pintype "passive"))
    )
    (net (code "72") (name "Net-(LED3-C1)") (class "Default")
      (node (ref "LED3") (pin "1") (pinfunction "C1_1") (pintype "power_in"))
      (node (ref "R221") (pin "1") (pinfunction "1_1") (pintype "passive"))
    )
    (net (code "73") (name "Net-(LED3-C2)") (class "Default")
      (node (ref "LED3") (pin "2") (pinfunction "C2_2") (pintype "power_in"))
      (node (ref "R222") (pin "1") (pinfunction "1_1") (pintype "passive"))
    )
    (net (code "74") (name "Net-(LED4-C1)") (class "Default")
      (node (ref "LED4") (pin "1") (pinfunction "C1_1") (pintype "power_in"))
      (node (ref "R226") (pin "1") (pinfunction "1_1") (pintype "passive"))
    )
    (net (code "75") (name "Net-(LED4-C2)") (class "Default")
      (node (ref "LED4") (pin "2") (pinfunction "C2_2") (pintype "power_in"))
      (node (ref "R229") (pin "1") (pinfunction "1_1") (pintype "passive"))
    )
    (net (code "76") (name "Net-(LED5-A)") (class "Default")
      (node (ref "LED5") (pin "3") (pinfunction "A_3") (pintype "power_in"))
      (node (ref "R239") (pin "2") (pinfunction "2_2") (pintype "passive"))
    )
    (net (code "77") (name "Net-(R242-Pad1)") (class "Default")
      (node (ref "R242") (pin "1") (pinfunction "1_1") (pintype "passive"))
      (node (ref "R243") (pin "2") (pinfunction "2_2") (pintype "passive"))
      (node (ref "R244") (pin "1") (pinfunction "1_1") (pintype "passive"))
    )
    (net (code "78") (name "VCC1P8A") (class "Default")
      (node (ref "C516") (pin "1") (pinfunction "1_1") (pintype "passive"))
      (node (ref "IC47") (pin "6") (pinfunction "VCCB_6") (pintype "power_in"))
    )
    (net (code "79") (name "VCC2P5") (class "Default")
      (node (ref "C515") (pin "2") (pinfunction "2_2") (pintype "passive"))
      (node (ref "IC47") (pin "1") (pinfunction "VCCA_1") (pintype "power_in"))
      (node (ref "R202") (pin "1") (pinfunction "1_1") (pintype "passive"))
      (node (ref "R203") (pin "1") (pinfunction "1_1") (pintype "passive"))
      (node (ref "R204") (pin "1") (pinfunction "1_1") (pintype "passive"))
      (node (ref "R205") (pin "1") (pinfunction "1_1") (pintype "passive"))
      (node (ref "R206") (pin "2") (pinfunction "2_2") (pintype "passive"))
    )
    (net (code "80") (name "VCC3P0_BATT") (class "Default")
      (node (ref "J20") (pin "2") (pinfunction "2_2") (pintype "passive"))
      (node (ref "R250") (pin "2") (pinfunction "2_2") (pintype "passive"))
    )
    (net (code "81") (name "VCC3P3") (class "Default")
      (node (ref "C502") (pin "1") (pinfunction "1_1") (pintype "passive"))
      (node (ref "C508") (pin "1") (pinfunction "1_1") (pintype "passive"))
      (node (ref "C510") (pin "1") (pinfunction "1_1") (pintype "passive"))
      (node (ref "IC42") (pin "8") (pinfunction "VCC_8") (pintype "passive"))
      (node (ref "IC43") (pin "8") (pinfunction "VCC_8") (pintype "passive"))
      (node (ref "IC44") (pin "8") (pinfunction "VCC_8") (pintype "power_in"))
      (node (ref "IC45") (pin "8") (pinfunction "VCC_8") (pintype "power_in"))
      (node (ref "LED1") (pin "3") (pinfunction "A_3") (pintype "power_in"))
      (node (ref "LED2") (pin "3") (pinfunction "A_3") (pintype "power_in"))
      (node (ref "LED3") (pin "3") (pinfunction "A_3") (pintype "power_in"))
      (node (ref "LED4") (pin "3") (pinfunction "A_3") (pintype "power_in"))
      (node (ref "R213") (pin "1") (pinfunction "1_1") (pintype "passive"))
      (node (ref "R216") (pin "1") (pinfunction "1_1") (pintype "passive"))
      (node (ref "R218") (pin "2") (pinfunction "2_2") (pintype "passive"))
      (node (ref "R223") (pin "2") (pinfunction "2_2") (pintype "passive"))
      (node (ref "R239") (pin "1") (pinfunction "1_1") (pintype "passive"))
      (node (ref "R240") (pin "2") (pinfunction "2_2") (pintype "passive"))
    )
    (net (code "82") (name "VCC3P3_CLK") (class "Default")
      (node (ref "FR104") (pin "1") (pinfunction "1_1") (pintype "passive"))
    )
    (net (code "83") (name "VCC3P3_GNSS") (class "Default")
      (node (ref "C512") (pin "2") (pinfunction "2_2") (pintype "passive"))
      (node (ref "C513") (pin "2") (pinfunction "2_2") (pintype "passive"))
      (node (ref "C518") (pin "2") (pinfunction "2_2") (pintype "passive"))
      (node (ref "C519") (pin "1") (pinfunction "1_1") (pintype "passive"))
      (node (ref "FR104") (pin "2") (pinfunction "2_2") (pintype "passive"))
      (node (ref "IC46") (pin "23") (pinfunction "VCC_23") (pintype "passive"))
      (node (ref "R243") (pin "1") (pinfunction "1_1") (pintype "passive"))
      (node (ref "R245") (pin "2") (pinfunction "2_2") (pintype "passive"))
      (node (ref "R251") (pin "2") (pinfunction "2_2") (pintype "passive"))
    )
    (net (code "84") (name "VCC5P0") (class "Default")
      (node (ref "R219") (pin "1") (pinfunction "1_1") (pintype "passive"))
      (node (ref "R224") (pin "2") (pinfunction "2_2") (pintype "passive"))
      (node (ref "R241") (pin "1") (pinfunction "1_1") (pintype "passive"))
    )
    (net (code "85") (name "VCC12P0") (class "Default")
      (node (ref "R225") (pin "2") (pinfunction "2_2") (pintype "passive"))
    )
    (net (code "86") (name "unconnected-(IC44-NC-Pad1)") (class "Default")
      (node (ref "IC44") (pin "1") (pinfunction "NC_1") (pintype "passive+no_connect"))
    )
    (net (code "87") (name "unconnected-(IC44-NC-Pad2)") (class "Default")
      (node (ref "IC44") (pin "2") (pinfunction "NC_2") (pintype "passive+no_connect"))
    )
    (net (code "88") (name "unconnected-(IC44-NC-Pad3)") (class "Default")
      (node (ref "IC44") (pin "3") (pinfunction "NC_3") (pintype "passive+no_connect"))
    )
    (net (code "89") (name "unconnected-(IC44-NC-Pad7)") (class "Default")
      (node (ref "IC44") (pin "7") (pinfunction "NC_7") (pintype "passive+no_connect"))
    )
    (net (code "90") (name "unconnected-(IC45-NC-Pad1)") (class "Default")
      (node (ref "IC45") (pin "1") (pinfunction "NC_1") (pintype "passive+no_connect"))
    )
    (net (code "91") (name "unconnected-(IC45-NC-Pad2)") (class "Default")
      (node (ref "IC45") (pin "2") (pinfunction "NC_2") (pintype "passive+no_connect"))
    )
    (net (code "92") (name "unconnected-(IC45-NC-Pad3)") (class "Default")
      (node (ref "IC45") (pin "3") (pinfunction "NC_3") (pintype "passive+no_connect"))
    )
    (net (code "93") (name "unconnected-(IC45-NC-Pad7)") (class "Default")
      (node (ref "IC45") (pin "7") (pinfunction "NC_7") (pintype "passive+no_connect"))
    )
    (net (code "94") (name "unconnected-(IC46-DDC_SCL{slash}SPI_CLK-Pad19)") (class "Default")
      (node (ref "IC46") (pin "19") (pinfunction "DDC_SCL/SPI_CLK_19") (pintype "passive+no_connect"))
    )
    (net (code "95") (name "unconnected-(IC46-DDC_SDA{slash}SPI_CSN-Pad18)") (class "Default")
      (node (ref "IC46") (pin "18") (pinfunction "DDC_SDA/SPI_CSN_18") (pintype "passive+no_connect"))
    )
    (net (code "96") (name "unconnected-(IC46-EXTINT-Pad4)") (class "Default")
      (node (ref "IC46") (pin "4") (pinfunction "EXTINT_4") (pintype "passive+no_connect"))
    )
    (net (code "97") (name "unconnected-(IC46-GEOFENCE_STAT{slash}RESV-Pad16)") (class "Default")
      (node (ref "IC46") (pin "16") (pinfunction "GEOFENCE_STAT/RESV_16") (pintype "passive+no_connect"))
    )
    (net (code "98") (name "unconnected-(IC46-LNA_EN{slash}RESV-Pad14)") (class "Default")
      (node (ref "IC46") (pin "14") (pinfunction "LNA_EN/RESV_14") (pintype "passive+no_connect"))
    )
    (net (code "99") (name "unconnected-(IC46-RESET_N-Pad8)") (class "Default")
      (node (ref "IC46") (pin "8") (pinfunction "RESET_N_8") (pintype "passive+no_connect"))
    )
    (net (code "100") (name "unconnected-(IC46-RESV-Pad17)") (class "Default")
      (node (ref "IC46") (pin "17") (pinfunction "RESV_17") (pintype "passive+no_connect"))
    )
    (net (code "101") (name "unconnected-(IC46-RTK_STAT{slash}RESV-Pad15)") (class "Default")
      (node (ref "IC46") (pin "15") (pinfunction "RTK_STAT/RESV_15") (pintype "passive+no_connect"))
    )
    (net (code "102") (name "unconnected-(IC46-USB_DM-Pad5)") (class "Default")
      (node (ref "IC46") (pin "5") (pinfunction "USB_DM_5") (pintype "passive+no_connect"))
    )
    (net (code "103") (name "unconnected-(IC46-USB_DP-Pad6)") (class "Default")
      (node (ref "IC46") (pin "6") (pinfunction "USB_DP_6") (pintype "passive+no_connect"))
    )
    (net (code "104") (name "unconnected-(LED5-C2-Pad2)") (class "Default")
      (node (ref "LED5") (pin "2") (pinfunction "C2_2") (pintype "power_in+no_connect"))
    )
  )
)
